# EsayEDA.net
KiCad netlist of a schematic drawn in EasyEDA
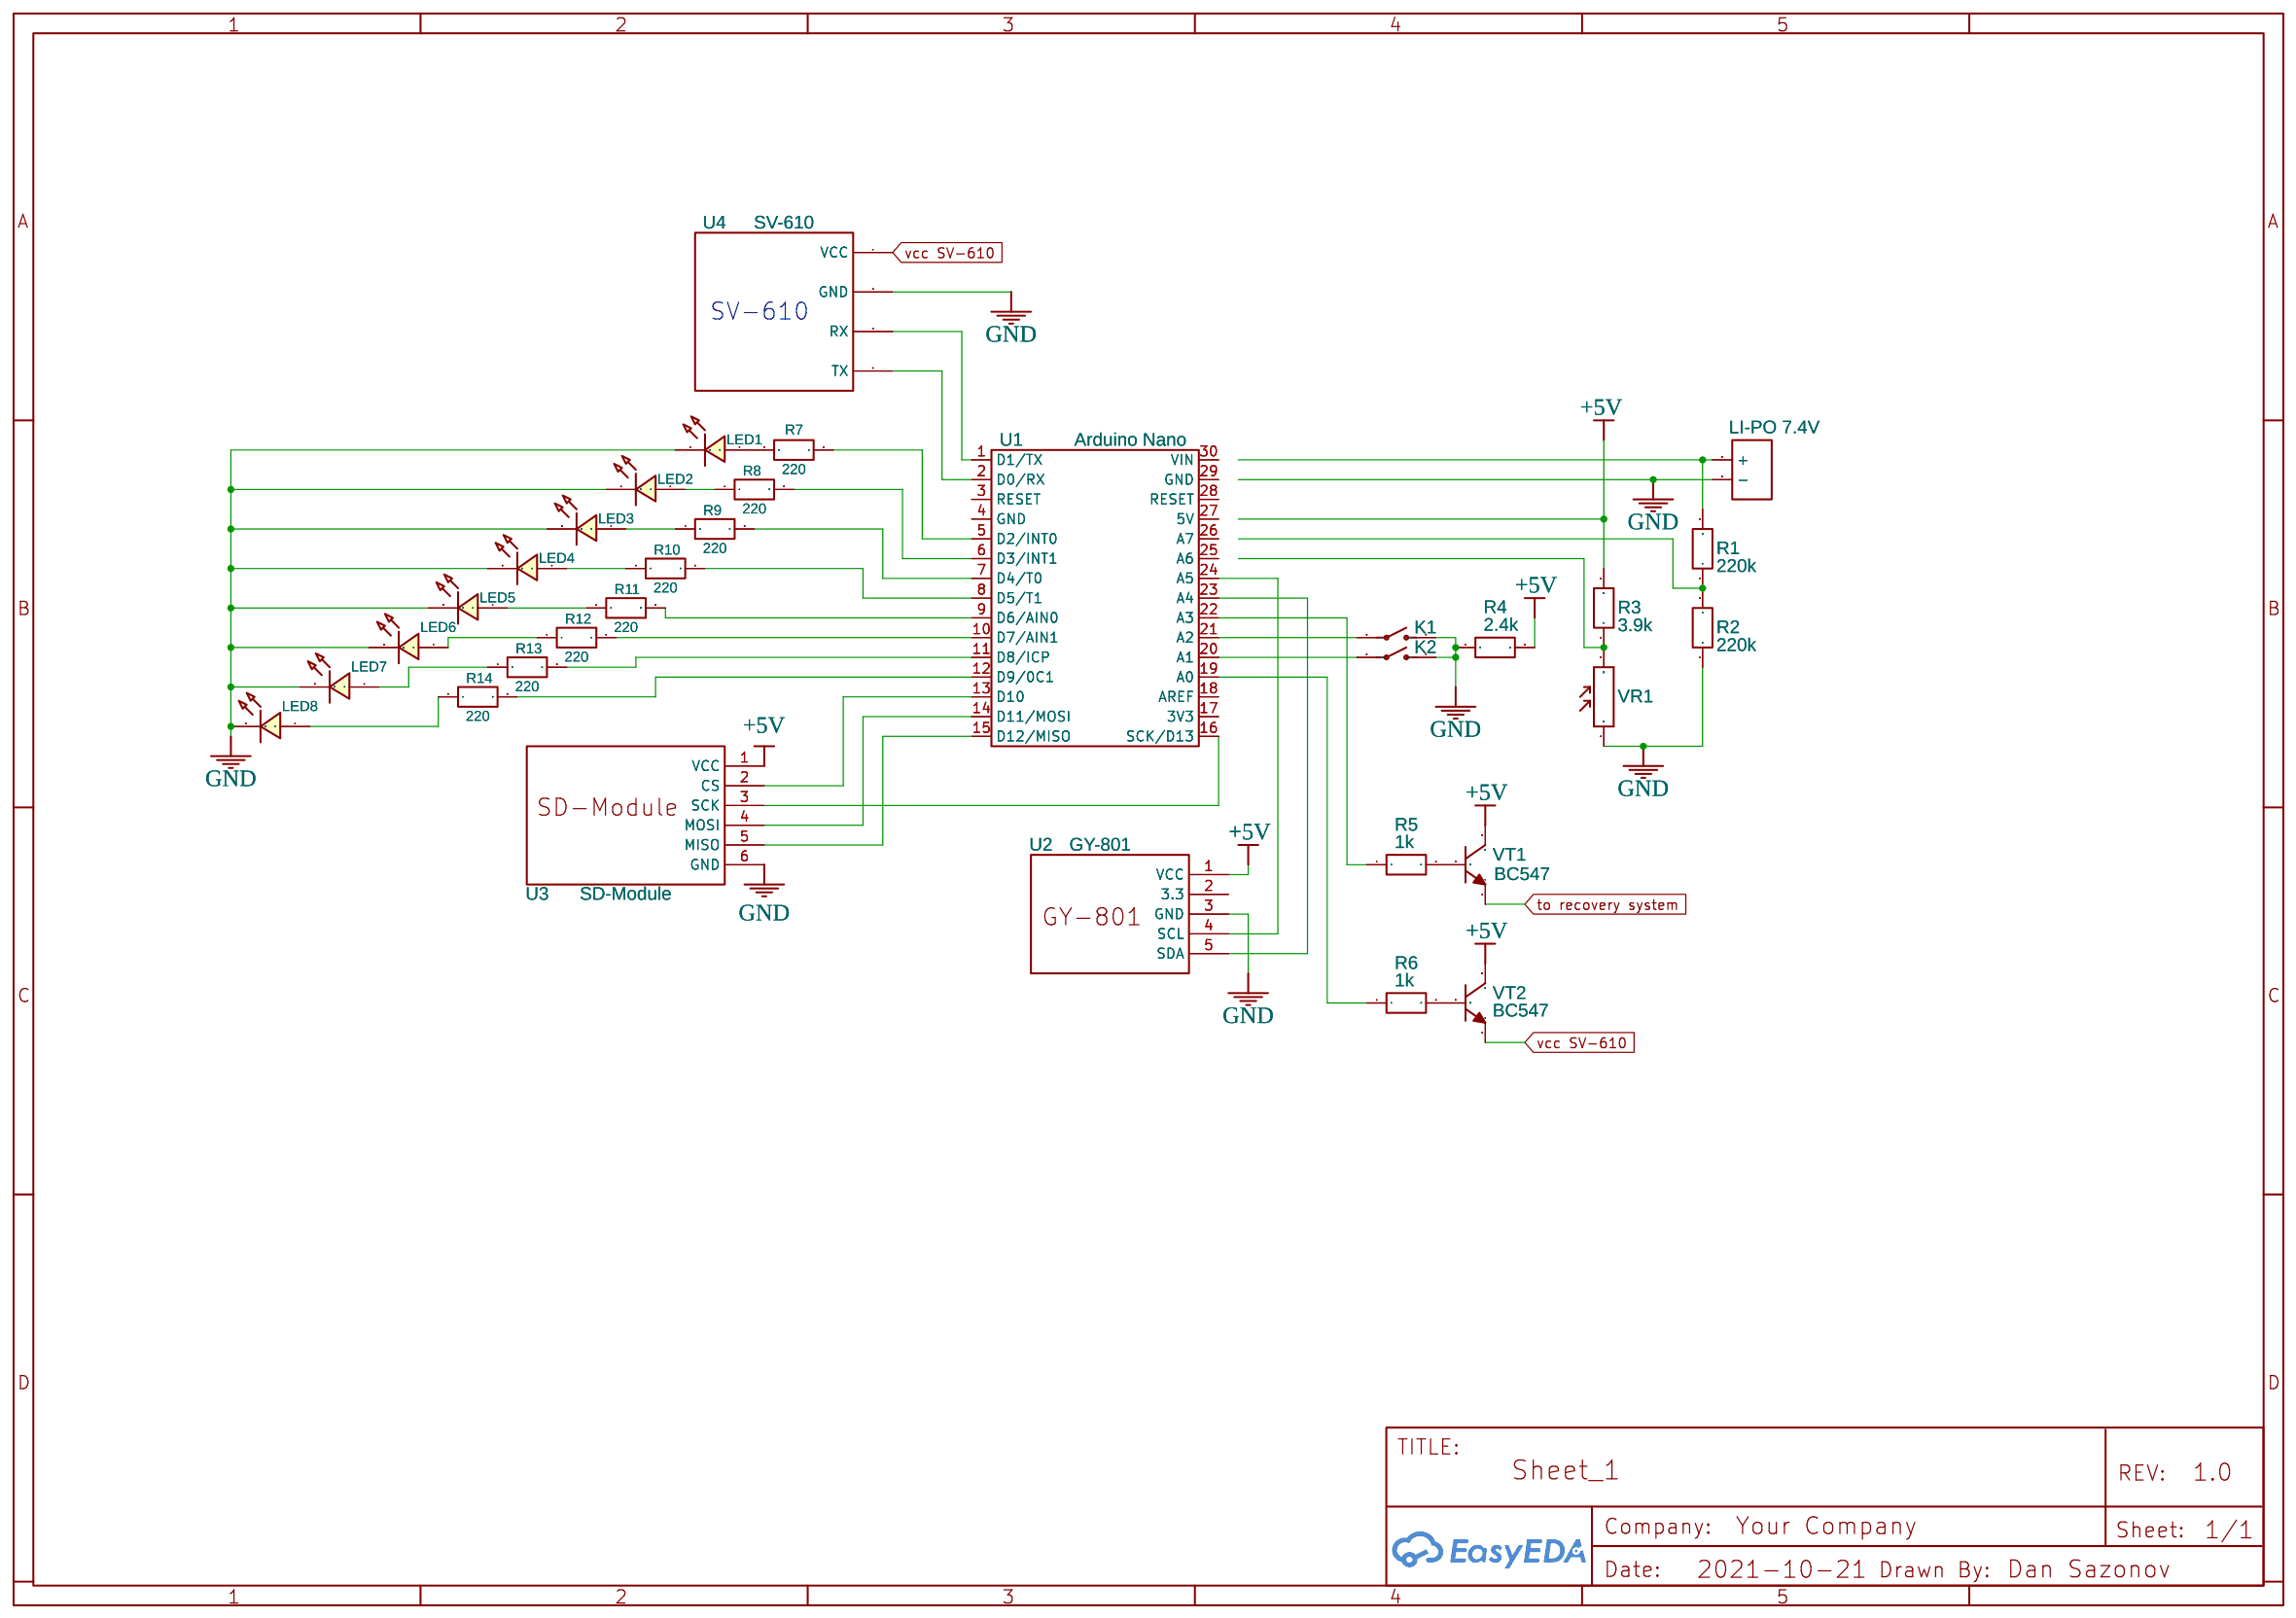
[diagram p0: schematic sheet]

(export (version "E")
  (design (tool "Eeschema 10.0.6"))
  (components
    (comp (ref "K1") (value "SWITCH-SPST-2TV") (libsource (lib "") (part "SWITCH-SPST-2TV")))
    (comp (ref "K2") (value "SWITCH-SPST-2TV") (libsource (lib "") (part "SWITCH-SPST-2TV")))
    (comp (ref "LED1")
      (value "LED-0603_R")
      (fields
        (field (name "BOM_Manufacturer Part") "19-217/R6C-AL1M2VY/3T")
        (field (name "BOM_Supplier Part") "C72044")
      )
      (libsource (lib "") (part "LED-0603_R"))
    )
    (comp (ref "LED2")
      (value "LED-0603_R")
      (fields
        (field (name "BOM_Manufacturer Part") "19-217/R6C-AL1M2VY/3T")
        (field (name "BOM_Supplier Part") "C72044")
      )
      (libsource (lib "") (part "LED-0603_R"))
    )
    (comp (ref "LED3")
      (value "LED-0603_R")
      (fields
        (field (name "BOM_Manufacturer Part") "19-217/R6C-AL1M2VY/3T")
        (field (name "BOM_Supplier Part") "C72044")
      )
      (libsource (lib "") (part "LED-0603_R"))
    )
    (comp (ref "LED4")
      (value "LED-0603_R")
      (fields
        (field (name "BOM_Manufacturer Part") "19-217/R6C-AL1M2VY/3T")
        (field (name "BOM_Supplier Part") "C72044")
      )
      (libsource (lib "") (part "LED-0603_R"))
    )
    (comp (ref "LED5")
      (value "LED-0603_R")
      (fields
        (field (name "BOM_Manufacturer Part") "19-217/R6C-AL1M2VY/3T")
        (field (name "BOM_Supplier Part") "C72044")
      )
      (libsource (lib "") (part "LED-0603_R"))
    )
    (comp (ref "LED6")
      (value "LED-0603_R")
      (fields
        (field (name "BOM_Manufacturer Part") "19-217/R6C-AL1M2VY/3T")
        (field (name "BOM_Supplier Part") "C72044")
      )
      (libsource (lib "") (part "LED-0603_R"))
    )
    (comp (ref "LED7")
      (value "LED-0603_R")
      (fields
        (field (name "BOM_Manufacturer Part") "19-217/R6C-AL1M2VY/3T")
        (field (name "BOM_Supplier Part") "C72044")
      )
      (libsource (lib "") (part "LED-0603_R"))
    )
    (comp (ref "LED8")
      (value "LED-0603_R")
      (fields
        (field (name "BOM_Manufacturer Part") "19-217/R6C-AL1M2VY/3T")
        (field (name "BOM_Supplier Part") "C72044")
      )
      (libsource (lib "") (part "LED-0603_R"))
    )
    (comp (ref "P1") (value "LI-PO 7.4V") (libsource (lib "") (part "CONN-TH_2P-P5.00")))
    (comp (ref "R1") (value "220k") (libsource (lib "") (part "R_0603_EU_1")))
    (comp (ref "R2") (value "220k") (libsource (lib "") (part "R_0603_EU_1")))
    (comp (ref "R3") (value "3.9k") (libsource (lib "") (part "R_0603_EU_1")))
    (comp (ref "R4") (value "2.4k") (libsource (lib "") (part "R_0603_EU")))
    (comp (ref "R5") (value "1k") (libsource (lib "") (part "R_0603_EU")))
    (comp (ref "R6") (value "1k") (libsource (lib "") (part "R_0603_EU")))
    (comp (ref "R7") (value "220") (libsource (lib "") (part "R_0603_EU")))
    (comp (ref "R8") (value "220") (libsource (lib "") (part "R_0603_EU")))
    (comp (ref "R9") (value "220") (libsource (lib "") (part "R_0603_EU")))
    (comp (ref "R10") (value "220") (libsource (lib "") (part "R_0603_EU")))
    (comp (ref "R11") (value "220") (libsource (lib "") (part "R_0603_EU")))
    (comp (ref "R12") (value "220") (libsource (lib "") (part "R_0603_EU")))
    (comp (ref "R13") (value "220") (libsource (lib "") (part "R_0603_EU")))
    (comp (ref "R14") (value "220") (libsource (lib "") (part "R_0603_EU")))
    (comp (ref "U1") (value "Arduino Nano") (libsource (lib "") (part "Arduino_Nano_Header")))
    (comp (ref "U2")
      (value "GY-801")
      (fields (field (name "BOM_Manufacturer Part") "GY-801 5 pin"))
      (libsource (lib "") (part "GY-801"))
    )
    (comp (ref "U3") (value "SD-Module") (libsource (lib "") (part "SD-Card-Module")))
    (comp (ref "U4") (value "SV-610") (libsource (lib "") (part "SV-610")))
    (comp (ref "VR1") (value "Photoresistor-5528") (libsource (lib "") (part "Photoresistor-5528")))
    (comp (ref "VT1")
      (value "BC547")
      (fields
        (field (name "BOM_Manufacturer Part") "2n3904S-RTK/PS")
        (field (name "BOM_Supplier Part") "C18536")
      )
      (libsource (lib "") (part "2N3904(SOT-23)"))
    )
    (comp (ref "VT2")
      (value "BC547")
      (fields
        (field (name "BOM_Manufacturer Part") "2n3904S-RTK/PS")
        (field (name "BOM_Supplier Part") "C18536")
      )
      (libsource (lib "") (part "2N3904(SOT-23)"))
    )
  )
  (nets
    (net (code "1") (name "+5V") (class "Default")
      (node (ref "R3") (pin "2") (pinfunction "2_2") (pintype "unspecified"))
      (node (ref "R4") (pin "2") (pinfunction "2_2") (pintype "unspecified"))
      (node (ref "U2") (pin "1") (pinfunction "VCC_1") (pintype "unspecified"))
      (node (ref "U3") (pin "1") (pinfunction "VCC_1") (pintype "unspecified"))
      (node (ref "VT1") (pin "3") (pinfunction "C_3") (pintype "input"))
      (node (ref "VT2") (pin "3") (pinfunction "C_3") (pintype "input"))
    )
    (net (code "2") (name "GND") (class "Default")
      (node (ref "K1") (pin "1") (pinfunction "O_1") (pintype "unspecified"))
      (node (ref "K2") (pin "1") (pinfunction "O_1") (pintype "unspecified"))
      (node (ref "LED1") (pin "2") (pinfunction "2_2") (pintype "unspecified"))
      (node (ref "LED2") (pin "2") (pinfunction "2_2") (pintype "unspecified"))
      (node (ref "LED3") (pin "2") (pinfunction "2_2") (pintype "unspecified"))
      (node (ref "LED4") (pin "2") (pinfunction "2_2") (pintype "unspecified"))
      (node (ref "LED5") (pin "2") (pinfunction "2_2") (pintype "unspecified"))
      (node (ref "LED6") (pin "2") (pinfunction "2_2") (pintype "unspecified"))
      (node (ref "LED7") (pin "2") (pinfunction "2_2") (pintype "unspecified"))
      (node (ref "LED8") (pin "2") (pinfunction "2_2") (pintype "unspecified"))
      (node (ref "P1") (pin "2") (pinfunction "-_2") (pintype "unspecified"))
      (node (ref "R2") (pin "1") (pinfunction "1_1") (pintype "unspecified"))
      (node (ref "R4") (pin "1") (pinfunction "1_1") (pintype "unspecified"))
      (node (ref "U2") (pin "3") (pinfunction "GND_3") (pintype "unspecified"))
      (node (ref "U3") (pin "6") (pinfunction "GND_6") (pintype "unspecified"))
      (node (ref "U4") (pin "3") (pinfunction "GND_3") (pintype "unspecified"))
      (node (ref "VR1") (pin "1") (pinfunction "P$1_1") (pintype "unspecified"))
    )
    (net (code "3") (name "Net-(K1-P)") (class "Default")
      (node (ref "K1") (pin "2") (pinfunction "P_2") (pintype "unspecified"))
      (node (ref "U1") (pin "21") (pinfunction "A2_21") (pintype "unspecified"))
    )
    (net (code "4") (name "Net-(K2-P)") (class "Default")
      (node (ref "K2") (pin "2") (pinfunction "P_2") (pintype "unspecified"))
      (node (ref "U1") (pin "20") (pinfunction "A1_20") (pintype "unspecified"))
    )
    (net (code "5") (name "Net-(LED1-Pad1)") (class "Default")
      (node (ref "LED1") (pin "1") (pinfunction "1_1") (pintype "unspecified"))
      (node (ref "R7") (pin "1") (pinfunction "1_1") (pintype "unspecified"))
    )
    (net (code "6") (name "Net-(LED2-Pad1)") (class "Default")
      (node (ref "LED2") (pin "1") (pinfunction "1_1") (pintype "unspecified"))
      (node (ref "R8") (pin "1") (pinfunction "1_1") (pintype "unspecified"))
    )
    (net (code "7") (name "Net-(LED3-Pad1)") (class "Default")
      (node (ref "LED3") (pin "1") (pinfunction "1_1") (pintype "unspecified"))
      (node (ref "R9") (pin "1") (pinfunction "1_1") (pintype "unspecified"))
    )
    (net (code "8") (name "Net-(LED4-Pad1)") (class "Default")
      (node (ref "LED4") (pin "1") (pinfunction "1_1") (pintype "unspecified"))
      (node (ref "R10") (pin "1") (pinfunction "1_1") (pintype "unspecified"))
    )
    (net (code "9") (name "Net-(LED5-Pad1)") (class "Default")
      (node (ref "LED5") (pin "1") (pinfunction "1_1") (pintype "unspecified"))
      (node (ref "R11") (pin "1") (pinfunction "1_1") (pintype "unspecified"))
    )
    (net (code "10") (name "Net-(LED6-Pad1)") (class "Default")
      (node (ref "LED6") (pin "1") (pinfunction "1_1") (pintype "unspecified"))
      (node (ref "R12") (pin "1") (pinfunction "1_1") (pintype "unspecified"))
    )
    (net (code "11") (name "Net-(LED7-Pad1)") (class "Default")
      (node (ref "LED7") (pin "1") (pinfunction "1_1") (pintype "unspecified"))
      (node (ref "R13") (pin "1") (pinfunction "1_1") (pintype "unspecified"))
    )
    (net (code "12") (name "Net-(LED8-Pad1)") (class "Default")
      (node (ref "LED8") (pin "1") (pinfunction "1_1") (pintype "unspecified"))
      (node (ref "R14") (pin "1") (pinfunction "1_1") (pintype "unspecified"))
    )
    (net (code "13") (name "Net-(P1-+)") (class "Default")
      (node (ref "P1") (pin "1") (pinfunction "+_1") (pintype "unspecified"))
      (node (ref "R1") (pin "2") (pinfunction "2_2") (pintype "unspecified"))
    )
    (net (code "14") (name "Net-(R1-Pad1)") (class "Default")
      (node (ref "R1") (pin "1") (pinfunction "1_1") (pintype "unspecified"))
      (node (ref "R2") (pin "2") (pinfunction "2_2") (pintype "unspecified"))
    )
    (net (code "15") (name "Net-(U1-A0)") (class "Default")
      (node (ref "R6") (pin "1") (pinfunction "1_1") (pintype "unspecified"))
      (node (ref "U1") (pin "19") (pinfunction "A0_19") (pintype "unspecified"))
    )
    (net (code "16") (name "Net-(U1-A3)") (class "Default")
      (node (ref "R5") (pin "1") (pinfunction "1_1") (pintype "unspecified"))
      (node (ref "U1") (pin "22") (pinfunction "A3_22") (pintype "unspecified"))
    )
    (net (code "17") (name "Net-(U1-A4)") (class "Default")
      (node (ref "U1") (pin "23") (pinfunction "A4_23") (pintype "unspecified"))
      (node (ref "U2") (pin "5") (pinfunction "SDA_5") (pintype "unspecified"))
    )
    (net (code "18") (name "Net-(U1-A5)") (class "Default")
      (node (ref "U1") (pin "24") (pinfunction "A5_24") (pintype "unspecified"))
      (node (ref "U2") (pin "4") (pinfunction "SCL_4") (pintype "unspecified"))
    )
    (net (code "19") (name "Net-(U1-D0{slash}RX)") (class "Default")
      (node (ref "U1") (pin "2") (pinfunction "D0/RX_2") (pintype "unspecified"))
      (node (ref "U4") (pin "1") (pinfunction "TX_1") (pintype "unspecified"))
    )
    (net (code "20") (name "Net-(U1-D1{slash}TX)") (class "Default")
      (node (ref "U1") (pin "1") (pinfunction "D1/TX_1") (pintype "unspecified"))
      (node (ref "U4") (pin "2") (pinfunction "RX_2") (pintype "unspecified"))
    )
    (net (code "21") (name "Net-(U1-D2{slash}INT0)") (class "Default")
      (node (ref "R7") (pin "2") (pinfunction "2_2") (pintype "unspecified"))
      (node (ref "U1") (pin "5") (pinfunction "D2/INT0_5") (pintype "unspecified"))
    )
    (net (code "22") (name "Net-(U1-D3{slash}INT1)") (class "Default")
      (node (ref "R8") (pin "2") (pinfunction "2_2") (pintype "unspecified"))
      (node (ref "U1") (pin "6") (pinfunction "D3/INT1_6") (pintype "unspecified"))
    )
    (net (code "23") (name "Net-(U1-D4{slash}T0)") (class "Default")
      (node (ref "R9") (pin "2") (pinfunction "2_2") (pintype "unspecified"))
      (node (ref "U1") (pin "7") (pinfunction "D4/T0_7") (pintype "unspecified"))
    )
    (net (code "24") (name "Net-(U1-D5{slash}T1)") (class "Default")
      (node (ref "R10") (pin "2") (pinfunction "2_2") (pintype "unspecified"))
      (node (ref "U1") (pin "8") (pinfunction "D5/T1_8") (pintype "unspecified"))
    )
    (net (code "25") (name "Net-(U1-D6{slash}AIN0)") (class "Default")
      (node (ref "R11") (pin "2") (pinfunction "2_2") (pintype "unspecified"))
      (node (ref "U1") (pin "9") (pinfunction "D6/AIN0_9") (pintype "unspecified"))
    )
    (net (code "26") (name "Net-(U1-D7{slash}AIN1)") (class "Default")
      (node (ref "R12") (pin "2") (pinfunction "2_2") (pintype "unspecified"))
      (node (ref "U1") (pin "10") (pinfunction "D7/AIN1_10") (pintype "unspecified"))
    )
    (net (code "27") (name "Net-(U1-D8{slash}ICP)") (class "Default")
      (node (ref "R13") (pin "2") (pinfunction "2_2") (pintype "unspecified"))
      (node (ref "U1") (pin "11") (pinfunction "D8/ICP_11") (pintype "unspecified"))
    )
    (net (code "28") (name "Net-(U1-D9{slash}0C1)") (class "Default")
      (node (ref "R14") (pin "2") (pinfunction "2_2") (pintype "unspecified"))
      (node (ref "U1") (pin "12") (pinfunction "D9/0C1_12") (pintype "unspecified"))
    )
    (net (code "29") (name "Net-(U1-D10)") (class "Default")
      (node (ref "U1") (pin "13") (pinfunction "D10_13") (pintype "unspecified"))
      (node (ref "U3") (pin "2") (pinfunction "CS_2") (pintype "unspecified"))
    )
    (net (code "30") (name "Net-(U1-D11{slash}MOSI)") (class "Default")
      (node (ref "U1") (pin "14") (pinfunction "D11/MOSI_14") (pintype "unspecified"))
      (node (ref "U3") (pin "4") (pinfunction "MOSI_4") (pintype "unspecified"))
    )
    (net (code "31") (name "Net-(U1-D12{slash}MISO)") (class "Default")
      (node (ref "U1") (pin "15") (pinfunction "D12/MISO_15") (pintype "unspecified"))
      (node (ref "U3") (pin "5") (pinfunction "MISO_5") (pintype "unspecified"))
    )
    (net (code "32") (name "Net-(U1-SCK{slash}D13)") (class "Default")
      (node (ref "U1") (pin "16") (pinfunction "SCK/D13_16") (pintype "unspecified"))
      (node (ref "U3") (pin "3") (pinfunction "SCK_3") (pintype "unspecified"))
    )
    (net (code "33") (name "Net-(VR1-P$2)") (class "Default")
      (node (ref "R3") (pin "1") (pinfunction "1_1") (pintype "unspecified"))
      (node (ref "VR1") (pin "2") (pinfunction "P$2_2") (pintype "unspecified"))
    )
    (net (code "34") (name "Net-(VT1-B)") (class "Default")
      (node (ref "R5") (pin "2") (pinfunction "2_2") (pintype "unspecified"))
      (node (ref "VT1") (pin "2") (pinfunction "B_2") (pintype "input"))
    )
    (net (code "35") (name "Net-(VT2-B)") (class "Default")
      (node (ref "R6") (pin "2") (pinfunction "2_2") (pintype "unspecified"))
      (node (ref "VT2") (pin "2") (pinfunction "B_2") (pintype "input"))
    )
    (net (code "36") (name "to recovery system") (class "Default")
      (node (ref "VT1") (pin "1") (pinfunction "E_1") (pintype "input"))
    )
    (net (code "37") (name "unconnected-(U1-3V3-Pad17)") (class "Default")
      (node (ref "U1") (pin "17") (pinfunction "3V3_17") (pintype "unspecified"))
    )
    (net (code "38") (name "unconnected-(U1-5V-Pad27)") (class "Default")
      (node (ref "U1") (pin "27") (pinfunction "5V_27") (pintype "unspecified"))
    )
    (net (code "39") (name "unconnected-(U1-A6-Pad25)") (class "Default")
      (node (ref "U1") (pin "25") (pinfunction "A6_25") (pintype "unspecified"))
    )
    (net (code "40") (name "unconnected-(U1-A7-Pad26)") (class "Default")
      (node (ref "U1") (pin "26") (pinfunction "A7_26") (pintype "unspecified"))
    )
    (net (code "41") (name "unconnected-(U1-AREF-Pad18)") (class "Default")
      (node (ref "U1") (pin "18") (pinfunction "AREF_18") (pintype "unspecified"))
    )
    (net (code "42") (name "unconnected-(U1-GND-Pad4)") (class "Default")
      (node (ref "U1") (pin "4") (pinfunction "GND_4") (pintype "unspecified"))
    )
    (net (code "43") (name "unconnected-(U1-GND-Pad29)") (class "Default")
      (node (ref "U1") (pin "29") (pinfunction "GND_29") (pintype "unspecified"))
    )
    (net (code "44") (name "unconnected-(U1-RESET-Pad3)") (class "Default")
      (node (ref "U1") (pin "3") (pinfunction "RESET_3") (pintype "unspecified"))
    )
    (net (code "45") (name "unconnected-(U1-RESET-Pad28)") (class "Default")
      (node (ref "U1") (pin "28") (pinfunction "RESET_28") (pintype "unspecified"))
    )
    (net (code "46") (name "unconnected-(U1-VIN-Pad30)") (class "Default")
      (node (ref "U1") (pin "30") (pinfunction "VIN_30") (pintype "unspecified"))
    )
    (net (code "47") (name "unconnected-(U2-3.3-Pad2)") (class "Default")
      (node (ref "U2") (pin "2") (pinfunction "3.3_2") (pintype "unspecified"))
    )
    (net (code "48") (name "vcc SV-610") (class "Default")
      (node (ref "U4") (pin "4") (pinfunction "VCC_4") (pintype "unspecified"))
      (node (ref "VT2") (pin "1") (pinfunction "E_1") (pintype "input"))
    )
  )
)
